# ST_LINK.net
KiCad netlist of a schematic drawn in Altium Designer
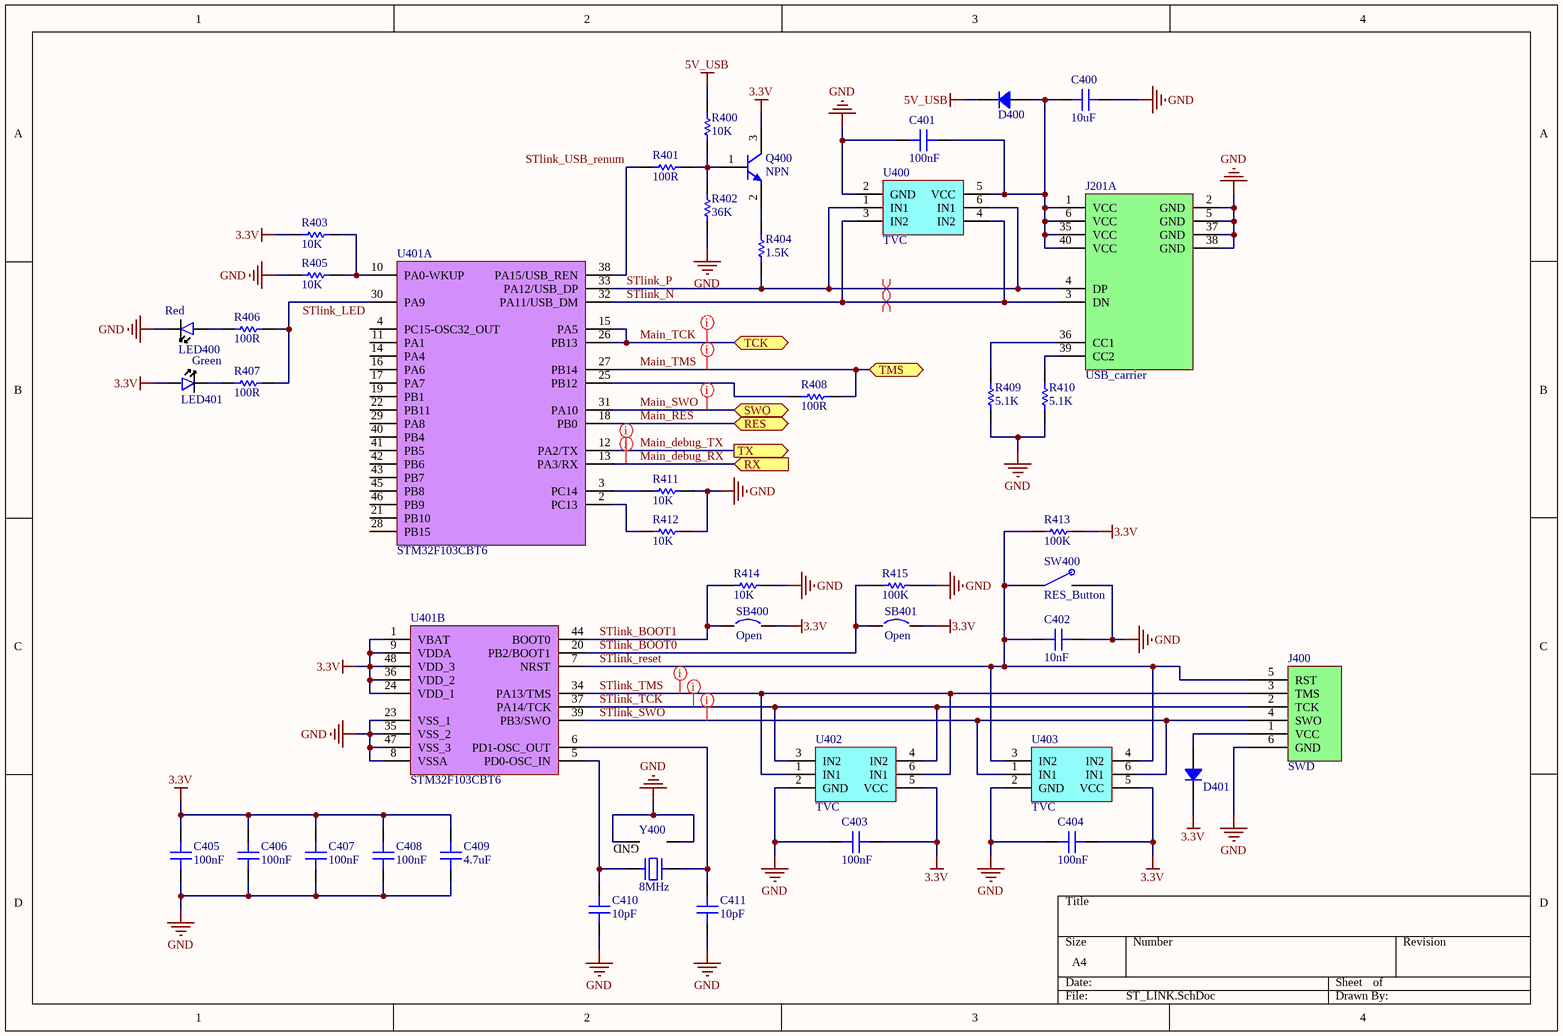
[diagram p0: ST_LINK.SchDoc]

(export (version "E")
  (design (tool "Eeschema 10.0.6"))
  (components
    (comp (ref "C400")
      (value "10uF")
      (footprint "CAP 0603")
      (description "SMT Capacitor")
      (libsource (lib "Schlib1") (part "Capacitor"))
    )
    (comp (ref "C401")
      (value "100nF")
      (footprint "CAP 0603")
      (description "SMT Capacitor")
      (libsource (lib "Schlib1") (part "Capacitor"))
    )
    (comp (ref "C402")
      (value "10nF")
      (footprint "CAP 0603")
      (description "SMT Capacitor")
      (libsource (lib "Schlib1") (part "Capacitor"))
    )
    (comp (ref "C403")
      (value "100nF")
      (footprint "CAP 0603")
      (description "SMT Capacitor")
      (libsource (lib "Schlib1") (part "Capacitor"))
    )
    (comp (ref "C404")
      (value "100nF")
      (footprint "CAP 0603")
      (description "SMT Capacitor")
      (libsource (lib "Schlib1") (part "Capacitor"))
    )
    (comp (ref "C405")
      (value "100nF")
      (footprint "CAP 0603")
      (description "SMT Capacitor")
      (libsource (lib "Schlib1") (part "Capacitor"))
    )
    (comp (ref "C406")
      (value "100nF")
      (footprint "CAP 0603")
      (description "SMT Capacitor")
      (libsource (lib "Schlib1") (part "Capacitor"))
    )
    (comp (ref "C407")
      (value "100nF")
      (footprint "CAP 0603")
      (description "SMT Capacitor")
      (libsource (lib "Schlib1") (part "Capacitor"))
    )
    (comp (ref "C408")
      (value "100nF")
      (footprint "CAP 0603")
      (description "SMT Capacitor")
      (libsource (lib "Schlib1") (part "Capacitor"))
    )
    (comp (ref "C409")
      (value "4.7uF")
      (footprint "CAP 1206")
      (description "SMT Capacitor")
      (libsource (lib "Schlib1") (part "Capacitor"))
    )
    (comp (ref "C410")
      (value "10pF")
      (footprint "CAP 0603")
      (description "SMT Capacitor")
      (libsource (lib "Schlib1") (part "Capacitor"))
    )
    (comp (ref "C411")
      (value "10pF")
      (footprint "CAP 0603")
      (description "SMT Capacitor")
      (libsource (lib "Schlib1") (part "Capacitor"))
    )
    (comp (ref "D400")
      (value "~")
      (footprint "Bourns DO214AC SMA - duplicate")
      (description "Rectifier Diode")
      (libsource (lib "Schlib1") (part "Diode"))
    )
    (comp (ref "D401")
      (value "~")
      (footprint "Bourns DO214AC SMA - duplicate")
      (description "Rectifier Diode")
      (libsource (lib "Schlib1") (part "Diode"))
    )
    (comp (ref "J201")
      (value "USB_carrier")
      (footprint "2167010409")
      (libsource (lib "Schlib1") (part "USB_carrier"))
    )
    (comp (ref "J400")
      (value "SWD")
      (footprint "AMPHENOL_20021121-00006C1LF")
      (libsource (lib "Schlib1") (part "SWD_connector"))
    )
    (comp (ref "LED400")
      (value "Red")
      (footprint "LED_0603")
      (fields (field (name "MFR PART #") "NCD1206B1") (field (name "LCSC PART#") "C130717"))
      (libsource (lib "Schlib1") (part "LED"))
    )
    (comp (ref "LED401")
      (value "Green")
      (footprint "LED_0603")
      (fields (field (name "MFR PART #") "NCD1206B1") (field (name "LCSC PART#") "C130717"))
      (libsource (lib "Schlib1") (part "LED"))
    )
    (comp (ref "Q400") (value "NPN") (footprint "SOT-23") (libsource (lib "Schlib1") (part "NPN")))
    (comp (ref "R400")
      (value "10K")
      (footprint "RES 0603")
      (description "Resistor")
      (fields (field (name "PUBLISHER") "Altium Limited"))
      (libsource (lib "Schlib1") (part "Res"))
    )
    (comp (ref "R401")
      (value "100R")
      (footprint "RES 0603")
      (description "Resistor")
      (fields (field (name "PUBLISHER") "Altium Limited"))
      (libsource (lib "Schlib1") (part "Res"))
    )
    (comp (ref "R402")
      (value "36K")
      (footprint "RES 0603")
      (description "Resistor")
      (fields (field (name "PUBLISHER") "Altium Limited"))
      (libsource (lib "Schlib1") (part "Res"))
    )
    (comp (ref "R403")
      (value "10K")
      (footprint "RES 0603")
      (description "Resistor")
      (fields (field (name "PUBLISHER") "Altium Limited"))
      (libsource (lib "Schlib1") (part "Res"))
    )
    (comp (ref "R404")
      (value "1.5K")
      (footprint "RES 0603")
      (description "Resistor")
      (fields (field (name "PUBLISHER") "Altium Limited"))
      (libsource (lib "Schlib1") (part "Res"))
    )
    (comp (ref "R405")
      (value "10K")
      (footprint "RES 0603")
      (description "Resistor")
      (fields (field (name "PUBLISHER") "Altium Limited"))
      (libsource (lib "Schlib1") (part "Res"))
    )
    (comp (ref "R406")
      (value "100R")
      (footprint "RES 0603")
      (description "Resistor")
      (fields (field (name "PUBLISHER") "Altium Limited"))
      (libsource (lib "Schlib1") (part "Res"))
    )
    (comp (ref "R407")
      (value "100R")
      (footprint "RES 0603")
      (description "Resistor")
      (fields (field (name "PUBLISHER") "Altium Limited"))
      (libsource (lib "Schlib1") (part "Res"))
    )
    (comp (ref "R408")
      (value "100R")
      (footprint "RES 0603")
      (description "Resistor")
      (fields (field (name "PUBLISHER") "Altium Limited"))
      (libsource (lib "Schlib1") (part "Res"))
    )
    (comp (ref "R409")
      (value "5.1K")
      (footprint "RES 0603")
      (description "Resistor")
      (fields (field (name "PUBLISHER") "Altium Limited"))
      (libsource (lib "Schlib1") (part "Res"))
    )
    (comp (ref "R410")
      (value "5.1K")
      (footprint "RES 0603")
      (description "Resistor")
      (fields (field (name "PUBLISHER") "Altium Limited"))
      (libsource (lib "Schlib1") (part "Res"))
    )
    (comp (ref "R411")
      (value "10K")
      (footprint "RES 0603")
      (description "Resistor")
      (fields (field (name "PUBLISHER") "Altium Limited"))
      (libsource (lib "Schlib1") (part "Res"))
    )
    (comp (ref "R412")
      (value "10K")
      (footprint "RES 0603")
      (description "Resistor")
      (fields (field (name "PUBLISHER") "Altium Limited"))
      (libsource (lib "Schlib1") (part "Res"))
    )
    (comp (ref "R413")
      (value "100K")
      (footprint "RES 0603")
      (description "Resistor")
      (fields (field (name "PUBLISHER") "Altium Limited"))
      (libsource (lib "Schlib1") (part "Res"))
    )
    (comp (ref "R414")
      (value "10K")
      (footprint "RES 0603")
      (description "Resistor")
      (fields (field (name "PUBLISHER") "Altium Limited"))
      (libsource (lib "Schlib1") (part "Res"))
    )
    (comp (ref "R415")
      (value "100K")
      (footprint "RES 0603")
      (description "Resistor")
      (fields (field (name "PUBLISHER") "Altium Limited"))
      (libsource (lib "Schlib1") (part "Res"))
    )
    (comp (ref "SB400")
      (value "Open")
      (footprint "SB_0603")
      (description "Circuit Breaker")
      (fields (field (name "PUBLISHER") "Altium Limited"))
      (libsource (lib "Schlib1") (part "Circuit Breaker"))
    )
    (comp (ref "SB401")
      (value "Open")
      (footprint "SB_0603")
      (description "Circuit Breaker")
      (fields (field (name "PUBLISHER") "Altium Limited"))
      (libsource (lib "Schlib1") (part "Circuit Breaker"))
    )
    (comp (ref "SW400")
      (value "RES_Button")
      (footprint "PTS636SM50JSMTRLFS")
      (libsource (lib "Schlib1") (part "RES_Button"))
    )
    (comp (ref "U400")
      (value "TVC")
      (footprint "ECEN_1400:DIODES SOT-23-6 W6")
      (libsource (lib "Schlib1") (part "USB_TVC_protection"))
    )
    (comp (ref "U401")
      (value "STM32F103CBT6")
      (footprint "TI PQFP-48 PAG0048A")
      (libsource (lib "Schlib1") (part "CMP-0237-00250-3"))
    )
    (comp (ref "U402")
      (value "TVC")
      (footprint "SOT95P275X110-6N - duplicate - duplicate")
      (libsource (lib "Schlib1") (part "TVC_protection"))
    )
    (comp (ref "U403")
      (value "TVC")
      (footprint "SOT95P275X110-6N - duplicate - duplicate")
      (libsource (lib "Schlib1") (part "TVC_protection"))
    )
    (comp (ref "Y400")
      (value "8MHz")
      (footprint "XTAL_ECS-80-10-33-CHN-TR3")
      (description "SMT Crystal")
      (libsource (lib "Schlib1") (part "Crystal 8Mhz"))
    )
  )
  (nets
    (net (code "1") (name "/Main_RES") (class "Default")
      (node (ref "U401") (pin "18") (pinfunction "PB0_18") (pintype "passive"))
    )
    (net (code "2") (name "/Main_SWO") (class "Default")
      (node (ref "U401") (pin "31") (pinfunction "PA10_31") (pintype "passive"))
    )
    (net (code "3") (name "/Main_TCK") (class "Default")
      (node (ref "U401") (pin "15") (pinfunction "PA5_15") (pintype "passive"))
      (node (ref "U401") (pin "26") (pinfunction "PB13_26") (pintype "passive"))
    )
    (net (code "4") (name "/Main_TMS") (class "Default")
      (node (ref "R408") (pin "2") (pinfunction "2_2") (pintype "passive"))
      (node (ref "U401") (pin "27") (pinfunction "PB14_27") (pintype "passive"))
    )
    (net (code "5") (name "/Main_debug_RX") (class "Default")
      (node (ref "U401") (pin "13") (pinfunction "PA3/RX_13") (pintype "passive"))
    )
    (net (code "6") (name "/Main_debug_TX") (class "Default")
      (node (ref "U401") (pin "12") (pinfunction "PA2/TX_12") (pintype "passive"))
    )
    (net (code "7") (name "/STlink_BOOT0") (class "Default")
      (node (ref "R415") (pin "1") (pinfunction "1_1") (pintype "passive"))
      (node (ref "SB401") (pin "1") (pinfunction "1_1") (pintype "passive"))
      (node (ref "U401") (pin "20") (pinfunction "PB2/BOOT1_20") (pintype "passive"))
    )
    (net (code "8") (name "/STlink_BOOT1") (class "Default")
      (node (ref "R414") (pin "1") (pinfunction "1_1") (pintype "passive"))
      (node (ref "SB400") (pin "1") (pinfunction "1_1") (pintype "passive"))
      (node (ref "U401") (pin "44") (pinfunction "BOOT0_44") (pintype "passive"))
    )
    (net (code "9") (name "/STlink_LED") (class "Default")
      (node (ref "R406") (pin "2") (pinfunction "2_2") (pintype "passive"))
      (node (ref "R407") (pin "2") (pinfunction "2_2") (pintype "passive"))
      (node (ref "U401") (pin "30") (pinfunction "PA9_30") (pintype "passive"))
    )
    (net (code "10") (name "/STlink_N") (class "Default")
      (node (ref "J201") (pin "3") (pinfunction "DN_3") (pintype "passive"))
      (node (ref "U400") (pin "3") (pinfunction "IN2_3") (pintype "passive"))
      (node (ref "U400") (pin "4") (pinfunction "IN2_4") (pintype "passive"))
      (node (ref "U401") (pin "32") (pinfunction "PA11/USB_DM_32") (pintype "passive"))
    )
    (net (code "11") (name "/STlink_P") (class "Default")
      (node (ref "J201") (pin "4") (pinfunction "DP_4") (pintype "passive"))
      (node (ref "R404") (pin "1") (pinfunction "1_1") (pintype "passive"))
      (node (ref "U400") (pin "1") (pinfunction "IN1_1") (pintype "passive"))
      (node (ref "U400") (pin "6") (pinfunction "IN1_6") (pintype "passive"))
      (node (ref "U401") (pin "33") (pinfunction "PA12/USB_DP_33") (pintype "passive"))
    )
    (net (code "12") (name "/STlink_SWO") (class "Default")
      (node (ref "J400") (pin "4") (pinfunction "SWO_4") (pintype "passive"))
      (node (ref "U401") (pin "39") (pinfunction "PB3/SWO_39") (pintype "passive"))
      (node (ref "U403") (pin "1") (pinfunction "IN1_1") (pintype "passive"))
      (node (ref "U403") (pin "6") (pinfunction "IN1_6") (pintype "passive"))
    )
    (net (code "13") (name "/STlink_TCK") (class "Default")
      (node (ref "J400") (pin "2") (pinfunction "TCK_2") (pintype "passive"))
      (node (ref "U401") (pin "37") (pinfunction "PA14/TCK_37") (pintype "passive"))
      (node (ref "U402") (pin "3") (pinfunction "IN2_3") (pintype "passive"))
      (node (ref "U402") (pin "4") (pinfunction "IN2_4") (pintype "passive"))
    )
    (net (code "14") (name "/STlink_TMS") (class "Default")
      (node (ref "J400") (pin "3") (pinfunction "TMS_3") (pintype "passive"))
      (node (ref "U401") (pin "34") (pinfunction "PA13/TMS_34") (pintype "passive"))
      (node (ref "U402") (pin "1") (pinfunction "IN1_1") (pintype "passive"))
      (node (ref "U402") (pin "6") (pinfunction "IN1_6") (pintype "passive"))
    )
    (net (code "15") (name "/STlink_USB_renum") (class "Default")
      (node (ref "R401") (pin "1") (pinfunction "1_1") (pintype "passive"))
      (node (ref "U401") (pin "38") (pinfunction "PA15/USB_REN_38") (pintype "passive"))
    )
    (net (code "16") (name "/STlink_reset") (class "Default")
      (node (ref "C402") (pin "2") (pinfunction "2_2") (pintype "passive"))
      (node (ref "J400") (pin "5") (pinfunction "RST_5") (pintype "passive"))
      (node (ref "R413") (pin "1") (pinfunction "1_1") (pintype "passive"))
      (node (ref "SW400") (pin "1") (pinfunction "1_1") (pintype "passive"))
      (node (ref "U401") (pin "7") (pinfunction "NRST_7") (pintype "passive"))
      (node (ref "U403") (pin "3") (pinfunction "IN2_3") (pintype "passive"))
      (node (ref "U403") (pin "4") (pinfunction "IN2_4") (pintype "passive"))
    )
    (net (code "17") (name "3.3V") (class "Default")
      (node (ref "C403") (pin "1") (pinfunction "1_1") (pintype "passive"))
      (node (ref "C404") (pin "1") (pinfunction "1_1") (pintype "passive"))
      (node (ref "C405") (pin "2") (pinfunction "2_2") (pintype "passive"))
      (node (ref "C406") (pin "2") (pinfunction "2_2") (pintype "passive"))
      (node (ref "C407") (pin "2") (pinfunction "2_2") (pintype "passive"))
      (node (ref "C408") (pin "2") (pinfunction "2_2") (pintype "passive"))
      (node (ref "C409") (pin "2") (pinfunction "2_2") (pintype "passive"))
      (node (ref "D401") (pin "2") (pinfunction "2_2") (pintype "passive"))
      (node (ref "LED401") (pin "1") (pinfunction "R_1") (pintype "passive"))
      (node (ref "Q400") (pin "3") (pinfunction "C_3") (pintype "passive"))
      (node (ref "R403") (pin "1") (pinfunction "1_1") (pintype "passive"))
      (node (ref "R413") (pin "2") (pinfunction "2_2") (pintype "passive"))
      (node (ref "SB400") (pin "2") (pinfunction "2_2") (pintype "passive"))
      (node (ref "SB401") (pin "2") (pinfunction "2_2") (pintype "passive"))
      (node (ref "U401") (pin "1") (pinfunction "VBAT_1") (pintype "power_in"))
      (node (ref "U401") (pin "24") (pinfunction "VDD_1_24") (pintype "power_in"))
      (node (ref "U401") (pin "36") (pinfunction "VDD_2_36") (pintype "power_in"))
      (node (ref "U401") (pin "48") (pinfunction "VDD_3_48") (pintype "power_in"))
      (node (ref "U401") (pin "9") (pinfunction "VDDA_9") (pintype "power_in"))
      (node (ref "U402") (pin "5") (pinfunction "VCC_5") (pintype "passive"))
      (node (ref "U403") (pin "5") (pinfunction "VCC_5") (pintype "passive"))
    )
    (net (code "18") (name "5V_USB") (class "Default")
      (node (ref "D400") (pin "2") (pinfunction "2_2") (pintype "passive"))
      (node (ref "R400") (pin "2") (pinfunction "2_2") (pintype "passive"))
    )
    (net (code "19") (name "GND") (class "Default")
      (node (ref "C400") (pin "1") (pinfunction "1_1") (pintype "passive"))
      (node (ref "C401") (pin "1") (pinfunction "1_1") (pintype "passive"))
      (node (ref "C402") (pin "1") (pinfunction "1_1") (pintype "passive"))
      (node (ref "C403") (pin "2") (pinfunction "2_2") (pintype "passive"))
      (node (ref "C404") (pin "2") (pinfunction "2_2") (pintype "passive"))
      (node (ref "C405") (pin "1") (pinfunction "1_1") (pintype "passive"))
      (node (ref "C406") (pin "1") (pinfunction "1_1") (pintype "passive"))
      (node (ref "C407") (pin "1") (pinfunction "1_1") (pintype "passive"))
      (node (ref "C408") (pin "1") (pinfunction "1_1") (pintype "passive"))
      (node (ref "C409") (pin "1") (pinfunction "1_1") (pintype "passive"))
      (node (ref "C410") (pin "1") (pinfunction "1_1") (pintype "passive"))
      (node (ref "C411") (pin "1") (pinfunction "1_1") (pintype "passive"))
      (node (ref "J201") (pin "2") (pinfunction "GND_2") (pintype "passive"))
      (node (ref "J201") (pin "37") (pinfunction "GND_37") (pintype "passive"))
      (node (ref "J201") (pin "38") (pinfunction "GND_38") (pintype "passive"))
      (node (ref "J201") (pin "5") (pinfunction "GND_5") (pintype "passive"))
      (node (ref "J400") (pin "6") (pinfunction "GND_6") (pintype "passive"))
      (node (ref "LED400") (pin "2") (pinfunction "Catode_2") (pintype "passive"))
      (node (ref "R402") (pin "1") (pinfunction "1_1") (pintype "passive"))
      (node (ref "R405") (pin "1") (pinfunction "1_1") (pintype "passive"))
      (node (ref "R409") (pin "1") (pinfunction "1_1") (pintype "passive"))
      (node (ref "R410") (pin "1") (pinfunction "1_1") (pintype "passive"))
      (node (ref "R411") (pin "2") (pinfunction "2_2") (pintype "passive"))
      (node (ref "R412") (pin "2") (pinfunction "2_2") (pintype "passive"))
      (node (ref "R414") (pin "2") (pinfunction "2_2") (pintype "passive"))
      (node (ref "R415") (pin "2") (pinfunction "2_2") (pintype "passive"))
      (node (ref "SW400") (pin "2") (pinfunction "2_2") (pintype "passive"))
      (node (ref "U400") (pin "2") (pinfunction "GND_2") (pintype "passive"))
      (node (ref "U401") (pin "23") (pinfunction "VSS_1_23") (pintype "power_in"))
      (node (ref "U401") (pin "35") (pinfunction "VSS_2_35") (pintype "power_in"))
      (node (ref "U401") (pin "47") (pinfunction "VSS_3_47") (pintype "power_in"))
      (node (ref "U401") (pin "8") (pinfunction "VSSA_8") (pintype "power_in"))
      (node (ref "U402") (pin "2") (pinfunction "GND_2") (pintype "passive"))
      (node (ref "U403") (pin "2") (pinfunction "GND_2") (pintype "passive"))
      (node (ref "Y400") (pin "2") (pinfunction "GND_2") (pintype "passive"))
      (node (ref "Y400") (pin "4") (pinfunction "GND_4") (pintype "passive"))
    )
    (net (code "20") (name "Net-(J201A-CC1)") (class "Default")
      (node (ref "J201") (pin "36") (pinfunction "CC1_36") (pintype "passive"))
      (node (ref "R409") (pin "2") (pinfunction "2_2") (pintype "passive"))
    )
    (net (code "21") (name "Net-(J201A-CC2)") (class "Default")
      (node (ref "J201") (pin "39") (pinfunction "CC2_39") (pintype "passive"))
      (node (ref "R410") (pin "2") (pinfunction "2_2") (pintype "passive"))
    )
    (net (code "22") (name "Net-(J400-VCC)") (class "Default")
      (node (ref "D401") (pin "1") (pinfunction "1_1") (pintype "passive"))
      (node (ref "J400") (pin "1") (pinfunction "VCC_1") (pintype "passive"))
    )
    (net (code "23") (name "Net-(LED400-R)") (class "Default")
      (node (ref "LED400") (pin "1") (pinfunction "R_1") (pintype "passive"))
      (node (ref "R406") (pin "1") (pinfunction "1_1") (pintype "passive"))
    )
    (net (code "24") (name "Net-(LED401-Catode)") (class "Default")
      (node (ref "LED401") (pin "2") (pinfunction "Catode_2") (pintype "passive"))
      (node (ref "R407") (pin "1") (pinfunction "1_1") (pintype "passive"))
    )
    (net (code "25") (name "Net-(Q400-B)") (class "Default")
      (node (ref "Q400") (pin "1") (pinfunction "B_1") (pintype "passive"))
      (node (ref "R400") (pin "1") (pinfunction "1_1") (pintype "passive"))
      (node (ref "R401") (pin "2") (pinfunction "2_2") (pintype "passive"))
      (node (ref "R402") (pin "2") (pinfunction "2_2") (pintype "passive"))
    )
    (net (code "26") (name "Net-(Q400-E)") (class "Default")
      (node (ref "Q400") (pin "2") (pinfunction "E_2") (pintype "passive"))
      (node (ref "R404") (pin "2") (pinfunction "2_2") (pintype "passive"))
    )
    (net (code "27") (name "Net-(U400-VCC)") (class "Default")
      (node (ref "C400") (pin "2") (pinfunction "2_2") (pintype "passive"))
      (node (ref "C401") (pin "2") (pinfunction "2_2") (pintype "passive"))
      (node (ref "D400") (pin "1") (pinfunction "1_1") (pintype "passive"))
      (node (ref "J201") (pin "1") (pinfunction "VCC_1") (pintype "passive"))
      (node (ref "J201") (pin "35") (pinfunction "VCC_35") (pintype "passive"))
      (node (ref "J201") (pin "40") (pinfunction "VCC_40") (pintype "passive"))
      (node (ref "J201") (pin "6") (pinfunction "VCC_6") (pintype "passive"))
      (node (ref "U400") (pin "5") (pinfunction "VCC_5") (pintype "passive"))
    )
    (net (code "28") (name "Net-(U401A-PA0-WKUP)") (class "Default")
      (node (ref "R403") (pin "2") (pinfunction "2_2") (pintype "passive"))
      (node (ref "R405") (pin "2") (pinfunction "2_2") (pintype "passive"))
      (node (ref "U401") (pin "10") (pinfunction "PA0-WKUP_10") (pintype "passive"))
    )
    (net (code "29") (name "Net-(U401A-PB12)") (class "Default")
      (node (ref "R408") (pin "1") (pinfunction "1_1") (pintype "passive"))
      (node (ref "U401") (pin "25") (pinfunction "PB12_25") (pintype "passive"))
    )
    (net (code "30") (name "Net-(U401A-PC13)") (class "Default")
      (node (ref "R412") (pin "1") (pinfunction "1_1") (pintype "passive"))
      (node (ref "U401") (pin "2") (pinfunction "PC13_2") (pintype "passive"))
    )
    (net (code "31") (name "Net-(U401A-PC14)") (class "Default")
      (node (ref "R411") (pin "1") (pinfunction "1_1") (pintype "passive"))
      (node (ref "U401") (pin "3") (pinfunction "PC14_3") (pintype "passive"))
    )
    (net (code "32") (name "Net-(U401B-PD0-OSC_IN)") (class "Default")
      (node (ref "C410") (pin "2") (pinfunction "2_2") (pintype "passive"))
      (node (ref "U401") (pin "5") (pinfunction "PD0-OSC_IN_5") (pintype "passive"))
      (node (ref "Y400") (pin "1") (pinfunction "1_1") (pintype "passive"))
    )
    (net (code "33") (name "Net-(U401B-PD1-OSC_OUT)") (class "Default")
      (node (ref "C411") (pin "2") (pinfunction "2_2") (pintype "passive"))
      (node (ref "U401") (pin "6") (pinfunction "PD1-OSC_OUT_6") (pintype "passive"))
      (node (ref "Y400") (pin "3") (pinfunction "3_3") (pintype "passive"))
    )
    (net (code "34") (name "unconnected-(U401A-PA1-Pad11)") (class "Default")
      (node (ref "U401") (pin "11") (pinfunction "PA1_11") (pintype "passive"))
    )
    (net (code "35") (name "unconnected-(U401A-PA4-Pad14)") (class "Default")
      (node (ref "U401") (pin "14") (pinfunction "PA4_14") (pintype "passive"))
    )
    (net (code "36") (name "unconnected-(U401A-PA6-Pad16)") (class "Default")
      (node (ref "U401") (pin "16") (pinfunction "PA6_16") (pintype "passive"))
    )
    (net (code "37") (name "unconnected-(U401A-PA7-Pad17)") (class "Default")
      (node (ref "U401") (pin "17") (pinfunction "PA7_17") (pintype "passive"))
    )
    (net (code "38") (name "unconnected-(U401A-PA8-Pad29)") (class "Default")
      (node (ref "U401") (pin "29") (pinfunction "PA8_29") (pintype "passive"))
    )
    (net (code "39") (name "unconnected-(U401A-PB1-Pad19)") (class "Default")
      (node (ref "U401") (pin "19") (pinfunction "PB1_19") (pintype "passive"))
    )
    (net (code "40") (name "unconnected-(U401A-PB4-Pad40)") (class "Default")
      (node (ref "U401") (pin "40") (pinfunction "PB4_40") (pintype "passive"))
    )
    (net (code "41") (name "unconnected-(U401A-PB5-Pad41)") (class "Default")
      (node (ref "U401") (pin "41") (pinfunction "PB5_41") (pintype "passive"))
    )
    (net (code "42") (name "unconnected-(U401A-PB6-Pad42)") (class "Default")
      (node (ref "U401") (pin "42") (pinfunction "PB6_42") (pintype "passive"))
    )
    (net (code "43") (name "unconnected-(U401A-PB7-Pad43)") (class "Default")
      (node (ref "U401") (pin "43") (pinfunction "PB7_43") (pintype "passive"))
    )
    (net (code "44") (name "unconnected-(U401A-PB8-Pad45)") (class "Default")
      (node (ref "U401") (pin "45") (pinfunction "PB8_45") (pintype "passive"))
    )
    (net (code "45") (name "unconnected-(U401A-PB9-Pad46)") (class "Default")
      (node (ref "U401") (pin "46") (pinfunction "PB9_46") (pintype "passive"))
    )
    (net (code "46") (name "unconnected-(U401A-PB10-Pad21)") (class "Default")
      (node (ref "U401") (pin "21") (pinfunction "PB10_21") (pintype "passive"))
    )
    (net (code "47") (name "unconnected-(U401A-PB11-Pad22)") (class "Default")
      (node (ref "U401") (pin "22") (pinfunction "PB11_22") (pintype "passive"))
    )
    (net (code "48") (name "unconnected-(U401A-PB15-Pad28)") (class "Default")
      (node (ref "U401") (pin "28") (pinfunction "PB15_28") (pintype "passive"))
    )
    (net (code "49") (name "unconnected-(U401A-PC15-OSC32_OUT-Pad4)") (class "Default")
      (node (ref "U401") (pin "4") (pinfunction "PC15-OSC32_OUT_4") (pintype "passive"))
    )
  )
)
